# SCH.net
KiCad netlist of a schematic drawn in EasyEDA
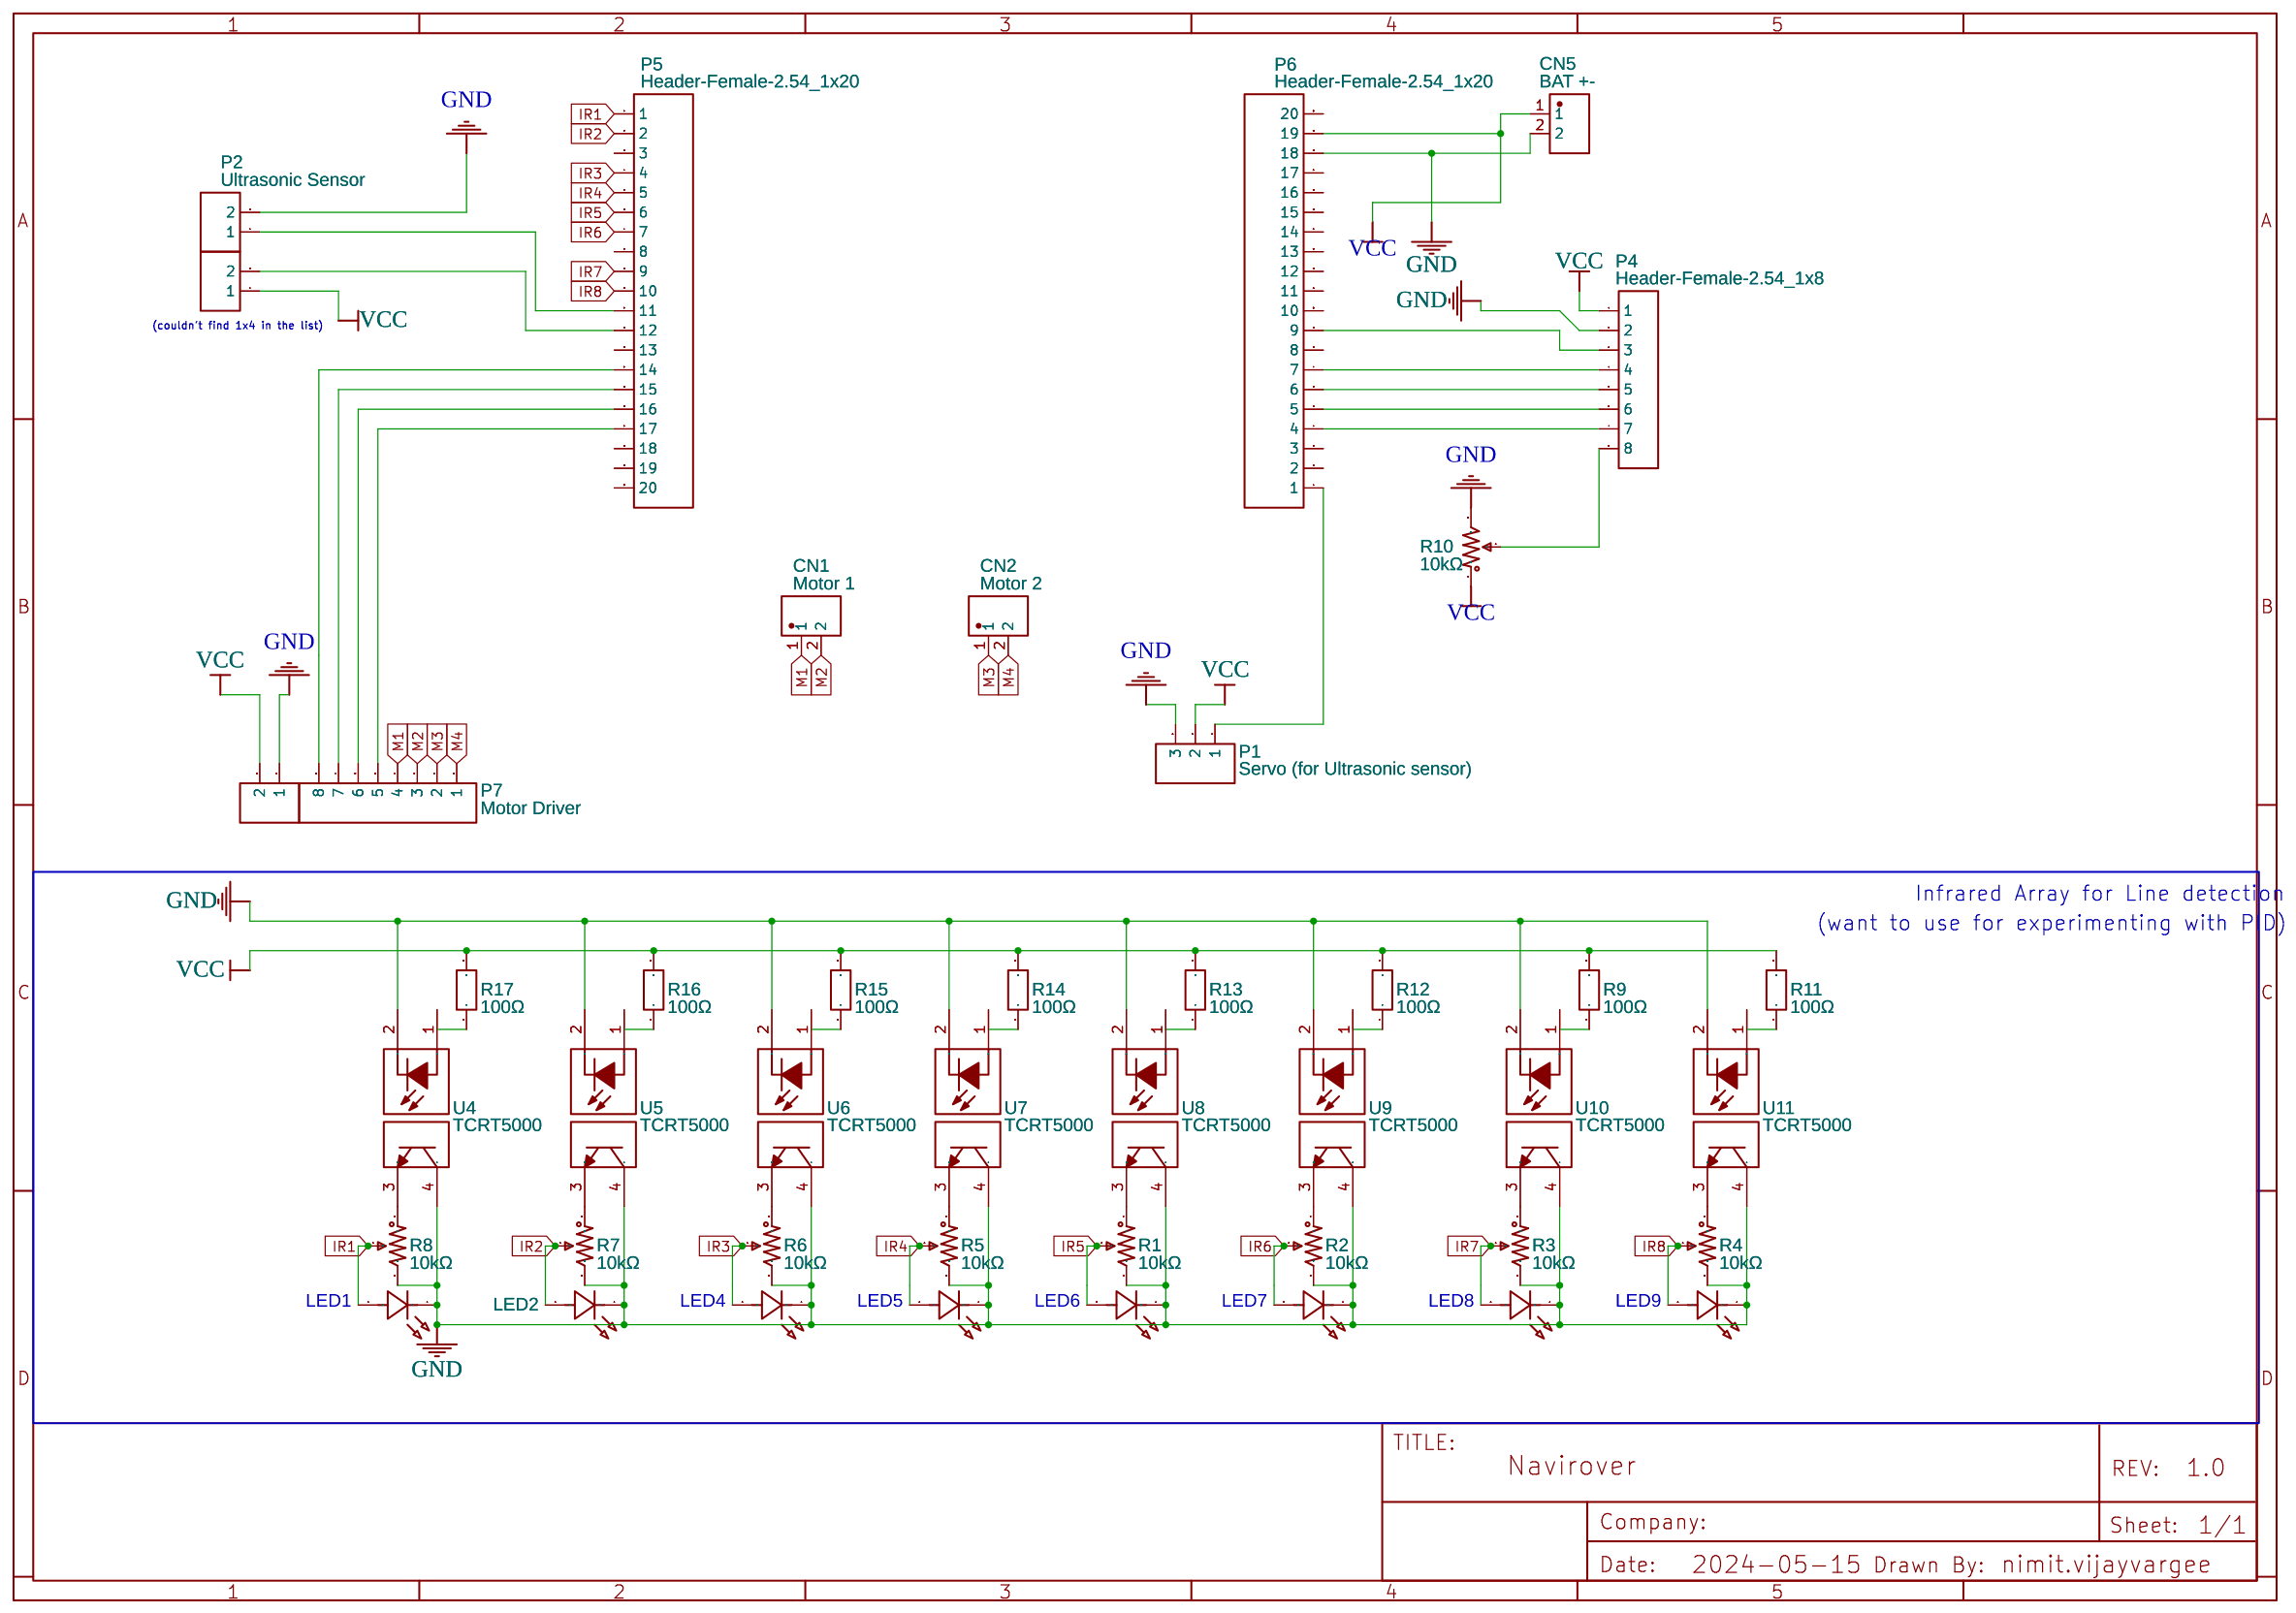
[diagram p0: schematic sheet]

(export (version "E")
  (design (tool "Eeschema 10.0.6"))
  (components
    (comp (ref "CN1")
      (value "Motor 1")
      (fields
        (field (name "Manufacturer Part") "MX301-5.0-02P-BU01-Cu-Y-A")
        (field (name "Manufacturer") "MAX(迈旭)")
      )
      (libsource (lib "") (part "MX301-5.0-02P-BU01-CU-Y-A"))
    )
    (comp (ref "CN2")
      (value "Motor 2")
      (fields
        (field (name "Manufacturer Part") "MX301-5.0-02P-BU01-Cu-Y-A")
        (field (name "Manufacturer") "MAX(迈旭)")
      )
      (libsource (lib "") (part "MX301-5.0-02P-BU01-CU-Y-A"))
    )
    (comp (ref "CN5")
      (value "BAT +-")
      (fields
        (field (name "Manufacturer Part") "MX301-5.0-02P-BU01-Cu-Y-A")
        (field (name "Manufacturer") "MAX(迈旭)")
      )
      (libsource (lib "") (part "MX301-5.0-02P-BU01-CU-Y-A_1"))
    )
    (comp (ref "LED1")
      (value "TJ-S1005CL4T5ALC3DW-A5")
      (fields (field (name "Manufacturer") "TOGIALED(统佳)"))
      (libsource (lib "") (part "TJ-S1005CL4T5ALC3DW-A5"))
    )
    (comp (ref "LED2")
      (value "TJ-S1005CL4T5ALC3DW-A5")
      (fields (field (name "Manufacturer") "TOGIALED(统佳)"))
      (libsource (lib "") (part "TJ-S1005CL4T5ALC3DW-A5"))
    )
    (comp (ref "LED3")
      (value "TJ-S1005CL4T5ALC3DW-A5")
      (fields (field (name "Manufacturer") "TOGIALED(统佳)"))
      (libsource (lib "") (part "TJ-S1005CL4T5ALC3DW-A5"))
    )
    (comp (ref "LED4")
      (value "TJ-S1005CL4T5ALC3DW-A5")
      (fields (field (name "Manufacturer") "TOGIALED(统佳)"))
      (libsource (lib "") (part "TJ-S1005CL4T5ALC3DW-A5"))
    )
    (comp (ref "LED5")
      (value "TJ-S1005CL4T5ALC3DW-A5")
      (fields (field (name "Manufacturer") "TOGIALED(统佳)"))
      (libsource (lib "") (part "TJ-S1005CL4T5ALC3DW-A5"))
    )
    (comp (ref "LED6")
      (value "TJ-S1005CL4T5ALC3DW-A5")
      (fields (field (name "Manufacturer") "TOGIALED(统佳)"))
      (libsource (lib "") (part "TJ-S1005CL4T5ALC3DW-A5"))
    )
    (comp (ref "LED7")
      (value "TJ-S1005CL4T5ALC3DW-A5")
      (fields (field (name "Manufacturer") "TOGIALED(统佳)"))
      (libsource (lib "") (part "TJ-S1005CL4T5ALC3DW-A5"))
    )
    (comp (ref "LED8")
      (value "TJ-S1005CL4T5ALC3DW-A5")
      (fields (field (name "Manufacturer") "TOGIALED(统佳)"))
      (libsource (lib "") (part "TJ-S1005CL4T5ALC3DW-A5"))
    )
    (comp (ref "P1")
      (value "Servo (for Ultrasonic sensor)")
      (fields (field (name "Manufacturer Part") "2.54-1*3P母") (field (name "Manufacturer") "BOOMELE(博穆精密)"))
      (libsource (lib "") (part "Header-Female-2.54_1x3"))
    )
    (comp (ref "P2")
      (value "Ultrasonic Sensor")
      (fields (field (name "Manufacturer Part") "2.54-1*2P母") (field (name "Manufacturer") "BOOMELE(博穆精密)"))
      (libsource (lib "") (part "Header-Female-2.54_1x2"))
    )
    (comp (ref "P3")
      (value "Header-Female-2.54_1x2")
      (fields (field (name "Manufacturer Part") "2.54-1*2P母") (field (name "Manufacturer") "BOOMELE(博穆精密)"))
      (libsource (lib "") (part "Header-Female-2.54_1x2"))
    )
    (comp (ref "P4")
      (value "Header-Female-2.54_1x8")
      (fields (field (name "Manufacturer Part") "2.54-1*8P母环保") (field (name "Manufacturer") "BOOMELE(博穆精密)"))
      (libsource (lib "") (part "Header-Female-2.54_1x8_1"))
    )
    (comp (ref "P5")
      (value "Header-Female-2.54_1x20")
      (fields (field (name "Manufacturer Part") "2.54-1*20P母") (field (name "Manufacturer") "BOOMELE(博穆精密)"))
      (libsource (lib "") (part "Header-Female-2.54_1x20_1"))
    )
    (comp (ref "P6")
      (value "Header-Female-2.54_1x20")
      (fields (field (name "Manufacturer Part") "2.54-1*20P母") (field (name "Manufacturer") "BOOMELE(博穆精密)"))
      (libsource (lib "") (part "Header-Female-2.54_1x20"))
    )
    (comp (ref "P7")
      (value "Motor Driver")
      (fields (field (name "Manufacturer Part") "2.54-1*8P母环保") (field (name "Manufacturer") "BOOMELE(博穆精密)"))
      (libsource (lib "") (part "Header-Female-2.54_1x8"))
    )
    (comp (ref "P8")
      (value "Header-Female-2.54_1x2")
      (fields (field (name "Manufacturer Part") "2.54-1*2P母") (field (name "Manufacturer") "BOOMELE(博穆精密)"))
      (libsource (lib "") (part "Header-Female-2.54_1x2_1"))
    )
    (comp (ref "R1")
      (value "10kΩ")
      (fields (field (name "Manufacturer Part") "3296W-1-103") (field (name "Manufacturer") "BOCHEN(博晨)"))
      (libsource (lib "") (part "3296W-1-103_1"))
    )
    (comp (ref "R2")
      (value "10kΩ")
      (fields (field (name "Manufacturer Part") "3296W-1-103") (field (name "Manufacturer") "BOCHEN(博晨)"))
      (libsource (lib "") (part "3296W-1-103_1"))
    )
    (comp (ref "R3")
      (value "10kΩ")
      (fields (field (name "Manufacturer Part") "3296W-1-103") (field (name "Manufacturer") "BOCHEN(博晨)"))
      (libsource (lib "") (part "3296W-1-103_1"))
    )
    (comp (ref "R4")
      (value "10kΩ")
      (fields (field (name "Manufacturer Part") "3296W-1-103") (field (name "Manufacturer") "BOCHEN(博晨)"))
      (libsource (lib "") (part "3296W-1-103_1"))
    )
    (comp (ref "R5")
      (value "10kΩ")
      (fields (field (name "Manufacturer Part") "3296W-1-103") (field (name "Manufacturer") "BOCHEN(博晨)"))
      (libsource (lib "") (part "3296W-1-103_1"))
    )
    (comp (ref "R6")
      (value "10kΩ")
      (fields (field (name "Manufacturer Part") "3296W-1-103") (field (name "Manufacturer") "BOCHEN(博晨)"))
      (libsource (lib "") (part "3296W-1-103_1"))
    )
    (comp (ref "R7")
      (value "10kΩ")
      (fields (field (name "Manufacturer Part") "3296W-1-103") (field (name "Manufacturer") "BOCHEN(博晨)"))
      (libsource (lib "") (part "3296W-1-103_1"))
    )
    (comp (ref "R8")
      (value "10kΩ")
      (fields (field (name "Manufacturer Part") "3296W-1-103") (field (name "Manufacturer") "BOCHEN(博晨)"))
      (libsource (lib "") (part "3296W-1-103_1"))
    )
    (comp (ref "R9")
      (value "100Ω")
      (fields
        (field (name "Manufacturer Part") "CQ05W8J0101T5E")
        (field (name "Manufacturer") "UNI-ROYAL(厚声)")
      )
      (libsource (lib "") (part "CQ05W8J0101T5E"))
    )
    (comp (ref "R10")
      (value "10kΩ")
      (fields (field (name "Manufacturer Part") "3296W-1-103") (field (name "Manufacturer") "BOCHEN(博晨)"))
      (libsource (lib "") (part "3296W-1-103"))
    )
    (comp (ref "R11")
      (value "100Ω")
      (fields
        (field (name "Manufacturer Part") "CQ05W8J0101T5E")
        (field (name "Manufacturer") "UNI-ROYAL(厚声)")
      )
      (libsource (lib "") (part "CQ05W8J0101T5E"))
    )
    (comp (ref "R12")
      (value "100Ω")
      (fields
        (field (name "Manufacturer Part") "CQ05W8J0101T5E")
        (field (name "Manufacturer") "UNI-ROYAL(厚声)")
      )
      (libsource (lib "") (part "CQ05W8J0101T5E"))
    )
    (comp (ref "R13")
      (value "100Ω")
      (fields
        (field (name "Manufacturer Part") "CQ05W8J0101T5E")
        (field (name "Manufacturer") "UNI-ROYAL(厚声)")
      )
      (libsource (lib "") (part "CQ05W8J0101T5E"))
    )
    (comp (ref "R14")
      (value "100Ω")
      (fields
        (field (name "Manufacturer Part") "CQ05W8J0101T5E")
        (field (name "Manufacturer") "UNI-ROYAL(厚声)")
      )
      (libsource (lib "") (part "CQ05W8J0101T5E"))
    )
    (comp (ref "R15")
      (value "100Ω")
      (fields
        (field (name "Manufacturer Part") "CQ05W8J0101T5E")
        (field (name "Manufacturer") "UNI-ROYAL(厚声)")
      )
      (libsource (lib "") (part "CQ05W8J0101T5E"))
    )
    (comp (ref "R16")
      (value "100Ω")
      (fields
        (field (name "Manufacturer Part") "CQ05W8J0101T5E")
        (field (name "Manufacturer") "UNI-ROYAL(厚声)")
      )
      (libsource (lib "") (part "CQ05W8J0101T5E"))
    )
    (comp (ref "R17")
      (value "100Ω")
      (fields
        (field (name "Manufacturer Part") "CQ05W8J0101T5E")
        (field (name "Manufacturer") "UNI-ROYAL(厚声)")
      )
      (libsource (lib "") (part "CQ05W8J0101T5E"))
    )
    (comp (ref "U4")
      (value "TCRT5000")
      (fields (field (name "Manufacturer") "VISHAY(威世)"))
      (libsource (lib "") (part "TCRT5000"))
    )
    (comp (ref "U5")
      (value "TCRT5000")
      (fields (field (name "Manufacturer") "VISHAY(威世)"))
      (libsource (lib "") (part "TCRT5000"))
    )
    (comp (ref "U6")
      (value "TCRT5000")
      (fields (field (name "Manufacturer") "VISHAY(威世)"))
      (libsource (lib "") (part "TCRT5000"))
    )
    (comp (ref "U7")
      (value "TCRT5000")
      (fields (field (name "Manufacturer") "VISHAY(威世)"))
      (libsource (lib "") (part "TCRT5000"))
    )
    (comp (ref "U8")
      (value "TCRT5000")
      (fields (field (name "Manufacturer") "VISHAY(威世)"))
      (libsource (lib "") (part "TCRT5000"))
    )
    (comp (ref "U9")
      (value "TCRT5000")
      (fields (field (name "Manufacturer") "VISHAY(威世)"))
      (libsource (lib "") (part "TCRT5000"))
    )
    (comp (ref "U10")
      (value "TCRT5000")
      (fields (field (name "Manufacturer") "VISHAY(威世)"))
      (libsource (lib "") (part "TCRT5000"))
    )
    (comp (ref "U11")
      (value "TCRT5000")
      (fields (field (name "Manufacturer") "VISHAY(威世)"))
      (libsource (lib "") (part "TCRT5000"))
    )
  )
  (nets
    (net (code "1") (name "GND") (class "Default")
      (node (ref "CN5") (pin "2") (pinfunction "2_2") (pintype "unspecified"))
      (node (ref "LED1") (pin "1") (pinfunction "K_1") (pintype "unspecified"))
      (node (ref "LED2") (pin "1") (pinfunction "K_1") (pintype "unspecified"))
      (node (ref "LED3") (pin "1") (pinfunction "K_1") (pintype "unspecified"))
      (node (ref "LED4") (pin "1") (pinfunction "K_1") (pintype "unspecified"))
      (node (ref "LED5") (pin "1") (pinfunction "K_1") (pintype "unspecified"))
      (node (ref "LED6") (pin "1") (pinfunction "K_1") (pintype "unspecified"))
      (node (ref "LED7") (pin "1") (pinfunction "K_1") (pintype "unspecified"))
      (node (ref "LED8") (pin "1") (pinfunction "K_1") (pintype "unspecified"))
      (node (ref "P1") (pin "3") (pinfunction "3_3") (pintype "input"))
      (node (ref "P2") (pin "2") (pinfunction "2_2") (pintype "input"))
      (node (ref "P4") (pin "2") (pinfunction "2_2") (pintype "input"))
      (node (ref "P6") (pin "18") (pinfunction "18_18") (pintype "input"))
      (node (ref "P8") (pin "1") (pinfunction "1_1") (pintype "input"))
      (node (ref "R1") (pin "3") (pinfunction "3_3") (pintype "unspecified"))
      (node (ref "R10") (pin "3") (pinfunction "3_3") (pintype "unspecified"))
      (node (ref "R2") (pin "3") (pinfunction "3_3") (pintype "unspecified"))
      (node (ref "R3") (pin "3") (pinfunction "3_3") (pintype "unspecified"))
      (node (ref "R4") (pin "3") (pinfunction "3_3") (pintype "unspecified"))
      (node (ref "R5") (pin "3") (pinfunction "3_3") (pintype "unspecified"))
      (node (ref "R6") (pin "3") (pinfunction "3_3") (pintype "unspecified"))
      (node (ref "R7") (pin "3") (pinfunction "3_3") (pintype "unspecified"))
      (node (ref "R8") (pin "3") (pinfunction "3_3") (pintype "unspecified"))
      (node (ref "U10") (pin "2") (pinfunction "2_2") (pintype "unspecified"))
      (node (ref "U10") (pin "4") (pinfunction "4_4") (pintype "unspecified"))
      (node (ref "U11") (pin "2") (pinfunction "2_2") (pintype "unspecified"))
      (node (ref "U11") (pin "4") (pinfunction "4_4") (pintype "unspecified"))
      (node (ref "U4") (pin "2") (pinfunction "2_2") (pintype "unspecified"))
      (node (ref "U4") (pin "4") (pinfunction "4_4") (pintype "unspecified"))
      (node (ref "U5") (pin "2") (pinfunction "2_2") (pintype "unspecified"))
      (node (ref "U5") (pin "4") (pinfunction "4_4") (pintype "unspecified"))
      (node (ref "U6") (pin "2") (pinfunction "2_2") (pintype "unspecified"))
      (node (ref "U6") (pin "4") (pinfunction "4_4") (pintype "unspecified"))
      (node (ref "U7") (pin "2") (pinfunction "2_2") (pintype "unspecified"))
      (node (ref "U7") (pin "4") (pinfunction "4_4") (pintype "unspecified"))
      (node (ref "U8") (pin "2") (pinfunction "2_2") (pintype "unspecified"))
      (node (ref "U8") (pin "4") (pinfunction "4_4") (pintype "unspecified"))
      (node (ref "U9") (pin "2") (pinfunction "2_2") (pintype "unspecified"))
      (node (ref "U9") (pin "4") (pinfunction "4_4") (pintype "unspecified"))
    )
    (net (code "2") (name "IR1") (class "Default")
      (node (ref "LED3") (pin "2") (pinfunction "A_2") (pintype "unspecified"))
      (node (ref "P5") (pin "1") (pinfunction "1_1") (pintype "input"))
      (node (ref "R8") (pin "2") (pinfunction "2_2") (pintype "unspecified"))
    )
    (net (code "3") (name "IR2") (class "Default")
      (node (ref "LED2") (pin "2") (pinfunction "A_2") (pintype "unspecified"))
      (node (ref "P5") (pin "2") (pinfunction "2_2") (pintype "input"))
      (node (ref "R7") (pin "2") (pinfunction "2_2") (pintype "unspecified"))
    )
    (net (code "4") (name "IR3") (class "Default")
      (node (ref "LED1") (pin "2") (pinfunction "A_2") (pintype "unspecified"))
      (node (ref "P5") (pin "4") (pinfunction "4_4") (pintype "input"))
      (node (ref "R6") (pin "2") (pinfunction "2_2") (pintype "unspecified"))
    )
    (net (code "5") (name "IR4") (class "Default")
      (node (ref "LED4") (pin "2") (pinfunction "A_2") (pintype "unspecified"))
      (node (ref "P5") (pin "5") (pinfunction "5_5") (pintype "input"))
      (node (ref "R5") (pin "2") (pinfunction "2_2") (pintype "unspecified"))
    )
    (net (code "6") (name "IR5") (class "Default")
      (node (ref "LED5") (pin "2") (pinfunction "A_2") (pintype "unspecified"))
      (node (ref "P5") (pin "6") (pinfunction "6_6") (pintype "input"))
      (node (ref "R1") (pin "2") (pinfunction "2_2") (pintype "unspecified"))
    )
    (net (code "7") (name "IR6") (class "Default")
      (node (ref "LED6") (pin "2") (pinfunction "A_2") (pintype "unspecified"))
      (node (ref "P5") (pin "7") (pinfunction "7_7") (pintype "input"))
      (node (ref "R2") (pin "2") (pinfunction "2_2") (pintype "unspecified"))
    )
    (net (code "8") (name "IR7") (class "Default")
      (node (ref "LED7") (pin "2") (pinfunction "A_2") (pintype "unspecified"))
      (node (ref "P5") (pin "9") (pinfunction "9_9") (pintype "input"))
      (node (ref "R3") (pin "2") (pinfunction "2_2") (pintype "unspecified"))
    )
    (net (code "9") (name "IR8") (class "Default")
      (node (ref "LED8") (pin "2") (pinfunction "A_2") (pintype "unspecified"))
      (node (ref "P5") (pin "10") (pinfunction "10_10") (pintype "input"))
      (node (ref "R4") (pin "2") (pinfunction "2_2") (pintype "unspecified"))
    )
    (net (code "10") (name "M1") (class "Default")
      (node (ref "CN1") (pin "1") (pinfunction "1_1") (pintype "unspecified"))
      (node (ref "P7") (pin "4") (pinfunction "4_4") (pintype "input"))
    )
    (net (code "11") (name "M2") (class "Default")
      (node (ref "CN1") (pin "2") (pinfunction "2_2") (pintype "unspecified"))
      (node (ref "P7") (pin "3") (pinfunction "3_3") (pintype "input"))
    )
    (net (code "12") (name "M3") (class "Default")
      (node (ref "CN2") (pin "1") (pinfunction "1_1") (pintype "unspecified"))
      (node (ref "P7") (pin "2") (pinfunction "2_2") (pintype "input"))
    )
    (net (code "13") (name "M4") (class "Default")
      (node (ref "CN2") (pin "2") (pinfunction "2_2") (pintype "unspecified"))
      (node (ref "P7") (pin "1") (pinfunction "1_1") (pintype "input"))
    )
    (net (code "14") (name "Net-(P1-Pad1)") (class "Default")
      (node (ref "P1") (pin "1") (pinfunction "1_1") (pintype "input"))
      (node (ref "P6") (pin "1") (pinfunction "1_1") (pintype "input"))
    )
    (net (code "15") (name "Net-(P2-Pad1)") (class "Default")
      (node (ref "P2") (pin "1") (pinfunction "1_1") (pintype "input"))
      (node (ref "P5") (pin "11") (pinfunction "11_11") (pintype "input"))
    )
    (net (code "16") (name "Net-(P3-Pad2)") (class "Default")
      (node (ref "P3") (pin "2") (pinfunction "2_2") (pintype "input"))
      (node (ref "P5") (pin "12") (pinfunction "12_12") (pintype "input"))
    )
    (net (code "17") (name "Net-(P4-Pad3)") (class "Default")
      (node (ref "P4") (pin "3") (pinfunction "3_3") (pintype "input"))
      (node (ref "P6") (pin "9") (pinfunction "9_9") (pintype "input"))
    )
    (net (code "18") (name "Net-(P4-Pad4)") (class "Default")
      (node (ref "P4") (pin "4") (pinfunction "4_4") (pintype "input"))
      (node (ref "P6") (pin "7") (pinfunction "7_7") (pintype "input"))
    )
    (net (code "19") (name "Net-(P4-Pad5)") (class "Default")
      (node (ref "P4") (pin "5") (pinfunction "5_5") (pintype "input"))
      (node (ref "P6") (pin "6") (pinfunction "6_6") (pintype "input"))
    )
    (net (code "20") (name "Net-(P4-Pad6)") (class "Default")
      (node (ref "P4") (pin "6") (pinfunction "6_6") (pintype "input"))
      (node (ref "P6") (pin "5") (pinfunction "5_5") (pintype "input"))
    )
    (net (code "21") (name "Net-(P4-Pad7)") (class "Default")
      (node (ref "P4") (pin "7") (pinfunction "7_7") (pintype "input"))
      (node (ref "P6") (pin "4") (pinfunction "4_4") (pintype "input"))
    )
    (net (code "22") (name "Net-(P4-Pad8)") (class "Default")
      (node (ref "P4") (pin "8") (pinfunction "8_8") (pintype "input"))
      (node (ref "R10") (pin "2") (pinfunction "2_2") (pintype "unspecified"))
    )
    (net (code "23") (name "Net-(P5-Pad14)") (class "Default")
      (node (ref "P5") (pin "14") (pinfunction "14_14") (pintype "input"))
      (node (ref "P7") (pin "8") (pinfunction "8_8") (pintype "input"))
    )
    (net (code "24") (name "Net-(P5-Pad15)") (class "Default")
      (node (ref "P5") (pin "15") (pinfunction "15_15") (pintype "input"))
      (node (ref "P7") (pin "7") (pinfunction "7_7") (pintype "input"))
    )
    (net (code "25") (name "Net-(P5-Pad16)") (class "Default")
      (node (ref "P5") (pin "16") (pinfunction "16_16") (pintype "input"))
      (node (ref "P7") (pin "6") (pinfunction "6_6") (pintype "input"))
    )
    (net (code "26") (name "Net-(P5-Pad17)") (class "Default")
      (node (ref "P5") (pin "17") (pinfunction "17_17") (pintype "input"))
      (node (ref "P7") (pin "5") (pinfunction "5_5") (pintype "input"))
    )
    (net (code "27") (name "Net-(R1-Pad1)") (class "Default")
      (node (ref "R1") (pin "1") (pinfunction "1_1") (pintype "unspecified"))
      (node (ref "U8") (pin "3") (pinfunction "3_3") (pintype "unspecified"))
    )
    (net (code "28") (name "Net-(R2-Pad1)") (class "Default")
      (node (ref "R2") (pin "1") (pinfunction "1_1") (pintype "unspecified"))
      (node (ref "U9") (pin "3") (pinfunction "3_3") (pintype "unspecified"))
    )
    (net (code "29") (name "Net-(R3-Pad1)") (class "Default")
      (node (ref "R3") (pin "1") (pinfunction "1_1") (pintype "unspecified"))
      (node (ref "U10") (pin "3") (pinfunction "3_3") (pintype "unspecified"))
    )
    (net (code "30") (name "Net-(R4-Pad1)") (class "Default")
      (node (ref "R4") (pin "1") (pinfunction "1_1") (pintype "unspecified"))
      (node (ref "U11") (pin "3") (pinfunction "3_3") (pintype "unspecified"))
    )
    (net (code "31") (name "Net-(R5-Pad1)") (class "Default")
      (node (ref "R5") (pin "1") (pinfunction "1_1") (pintype "unspecified"))
      (node (ref "U7") (pin "3") (pinfunction "3_3") (pintype "unspecified"))
    )
    (net (code "32") (name "Net-(R6-Pad1)") (class "Default")
      (node (ref "R6") (pin "1") (pinfunction "1_1") (pintype "unspecified"))
      (node (ref "U6") (pin "3") (pinfunction "3_3") (pintype "unspecified"))
    )
    (net (code "33") (name "Net-(R7-Pad1)") (class "Default")
      (node (ref "R7") (pin "1") (pinfunction "1_1") (pintype "unspecified"))
      (node (ref "U5") (pin "3") (pinfunction "3_3") (pintype "unspecified"))
    )
    (net (code "34") (name "Net-(R8-Pad1)") (class "Default")
      (node (ref "R8") (pin "1") (pinfunction "1_1") (pintype "unspecified"))
      (node (ref "U4") (pin "3") (pinfunction "3_3") (pintype "unspecified"))
    )
    (net (code "35") (name "Net-(R9-Pad1)") (class "Default")
      (node (ref "R9") (pin "1") (pinfunction "1_1") (pintype "unspecified"))
      (node (ref "U10") (pin "1") (pinfunction "1_1") (pintype "unspecified"))
    )
    (net (code "36") (name "Net-(R11-Pad1)") (class "Default")
      (node (ref "R11") (pin "1") (pinfunction "1_1") (pintype "unspecified"))
      (node (ref "U11") (pin "1") (pinfunction "1_1") (pintype "unspecified"))
    )
    (net (code "37") (name "Net-(R12-Pad1)") (class "Default")
      (node (ref "R12") (pin "1") (pinfunction "1_1") (pintype "unspecified"))
      (node (ref "U9") (pin "1") (pinfunction "1_1") (pintype "unspecified"))
    )
    (net (code "38") (name "Net-(R13-Pad1)") (class "Default")
      (node (ref "R13") (pin "1") (pinfunction "1_1") (pintype "unspecified"))
      (node (ref "U8") (pin "1") (pinfunction "1_1") (pintype "unspecified"))
    )
    (net (code "39") (name "Net-(R14-Pad1)") (class "Default")
      (node (ref "R14") (pin "1") (pinfunction "1_1") (pintype "unspecified"))
      (node (ref "U7") (pin "1") (pinfunction "1_1") (pintype "unspecified"))
    )
    (net (code "40") (name "Net-(R15-Pad1)") (class "Default")
      (node (ref "R15") (pin "1") (pinfunction "1_1") (pintype "unspecified"))
      (node (ref "U6") (pin "1") (pinfunction "1_1") (pintype "unspecified"))
    )
    (net (code "41") (name "Net-(R16-Pad1)") (class "Default")
      (node (ref "R16") (pin "1") (pinfunction "1_1") (pintype "unspecified"))
      (node (ref "U5") (pin "1") (pinfunction "1_1") (pintype "unspecified"))
    )
    (net (code "42") (name "Net-(R17-Pad1)") (class "Default")
      (node (ref "R17") (pin "1") (pinfunction "1_1") (pintype "unspecified"))
      (node (ref "U4") (pin "1") (pinfunction "1_1") (pintype "unspecified"))
    )
    (net (code "43") (name "VCC") (class "Default")
      (node (ref "CN5") (pin "1") (pinfunction "1_1") (pintype "unspecified"))
      (node (ref "P1") (pin "2") (pinfunction "2_2") (pintype "input"))
      (node (ref "P3") (pin "1") (pinfunction "1_1") (pintype "input"))
      (node (ref "P4") (pin "1") (pinfunction "1_1") (pintype "input"))
      (node (ref "P6") (pin "19") (pinfunction "19_19") (pintype "input"))
      (node (ref "P8") (pin "2") (pinfunction "2_2") (pintype "input"))
      (node (ref "R10") (pin "1") (pinfunction "1_1") (pintype "unspecified"))
      (node (ref "R11") (pin "2") (pinfunction "2_2") (pintype "unspecified"))
      (node (ref "R12") (pin "2") (pinfunction "2_2") (pintype "unspecified"))
      (node (ref "R13") (pin "2") (pinfunction "2_2") (pintype "unspecified"))
      (node (ref "R14") (pin "2") (pinfunction "2_2") (pintype "unspecified"))
      (node (ref "R15") (pin "2") (pinfunction "2_2") (pintype "unspecified"))
      (node (ref "R16") (pin "2") (pinfunction "2_2") (pintype "unspecified"))
      (node (ref "R17") (pin "2") (pinfunction "2_2") (pintype "unspecified"))
      (node (ref "R9") (pin "2") (pinfunction "2_2") (pintype "unspecified"))
    )
    (net (code "44") (name "unconnected-(P5-Pad3)") (class "Default")
      (node (ref "P5") (pin "3") (pinfunction "3_3") (pintype "input"))
    )
    (net (code "45") (name "unconnected-(P5-Pad8)") (class "Default")
      (node (ref "P5") (pin "8") (pinfunction "8_8") (pintype "input"))
    )
    (net (code "46") (name "unconnected-(P5-Pad13)") (class "Default")
      (node (ref "P5") (pin "13") (pinfunction "13_13") (pintype "input"))
    )
    (net (code "47") (name "unconnected-(P5-Pad18)") (class "Default")
      (node (ref "P5") (pin "18") (pinfunction "18_18") (pintype "input"))
    )
    (net (code "48") (name "unconnected-(P5-Pad19)") (class "Default")
      (node (ref "P5") (pin "19") (pinfunction "19_19") (pintype "input"))
    )
    (net (code "49") (name "unconnected-(P5-Pad20)") (class "Default")
      (node (ref "P5") (pin "20") (pinfunction "20_20") (pintype "input"))
    )
    (net (code "50") (name "unconnected-(P6-Pad2)") (class "Default")
      (node (ref "P6") (pin "2") (pinfunction "2_2") (pintype "input"))
    )
    (net (code "51") (name "unconnected-(P6-Pad3)") (class "Default")
      (node (ref "P6") (pin "3") (pinfunction "3_3") (pintype "input"))
    )
    (net (code "52") (name "unconnected-(P6-Pad8)") (class "Default")
      (node (ref "P6") (pin "8") (pinfunction "8_8") (pintype "input"))
    )
    (net (code "53") (name "unconnected-(P6-Pad10)") (class "Default")
      (node (ref "P6") (pin "10") (pinfunction "10_10") (pintype "input"))
    )
    (net (code "54") (name "unconnected-(P6-Pad11)") (class "Default")
      (node (ref "P6") (pin "11") (pinfunction "11_11") (pintype "input"))
    )
    (net (code "55") (name "unconnected-(P6-Pad12)") (class "Default")
      (node (ref "P6") (pin "12") (pinfunction "12_12") (pintype "input"))
    )
    (net (code "56") (name "unconnected-(P6-Pad13)") (class "Default")
      (node (ref "P6") (pin "13") (pinfunction "13_13") (pintype "input"))
    )
    (net (code "57") (name "unconnected-(P6-Pad14)") (class "Default")
      (node (ref "P6") (pin "14") (pinfunction "14_14") (pintype "input"))
    )
    (net (code "58") (name "unconnected-(P6-Pad15)") (class "Default")
      (node (ref "P6") (pin "15") (pinfunction "15_15") (pintype "input"))
    )
    (net (code "59") (name "unconnected-(P6-Pad16)") (class "Default")
      (node (ref "P6") (pin "16") (pinfunction "16_16") (pintype "input"))
    )
    (net (code "60") (name "unconnected-(P6-Pad17)") (class "Default")
      (node (ref "P6") (pin "17") (pinfunction "17_17") (pintype "input"))
    )
    (net (code "61") (name "unconnected-(P6-Pad20)") (class "Default")
      (node (ref "P6") (pin "20") (pinfunction "20_20") (pintype "input"))
    )
  )
)
